# Schematic_TSC.net
KiCad netlist of a schematic drawn in EAGLE
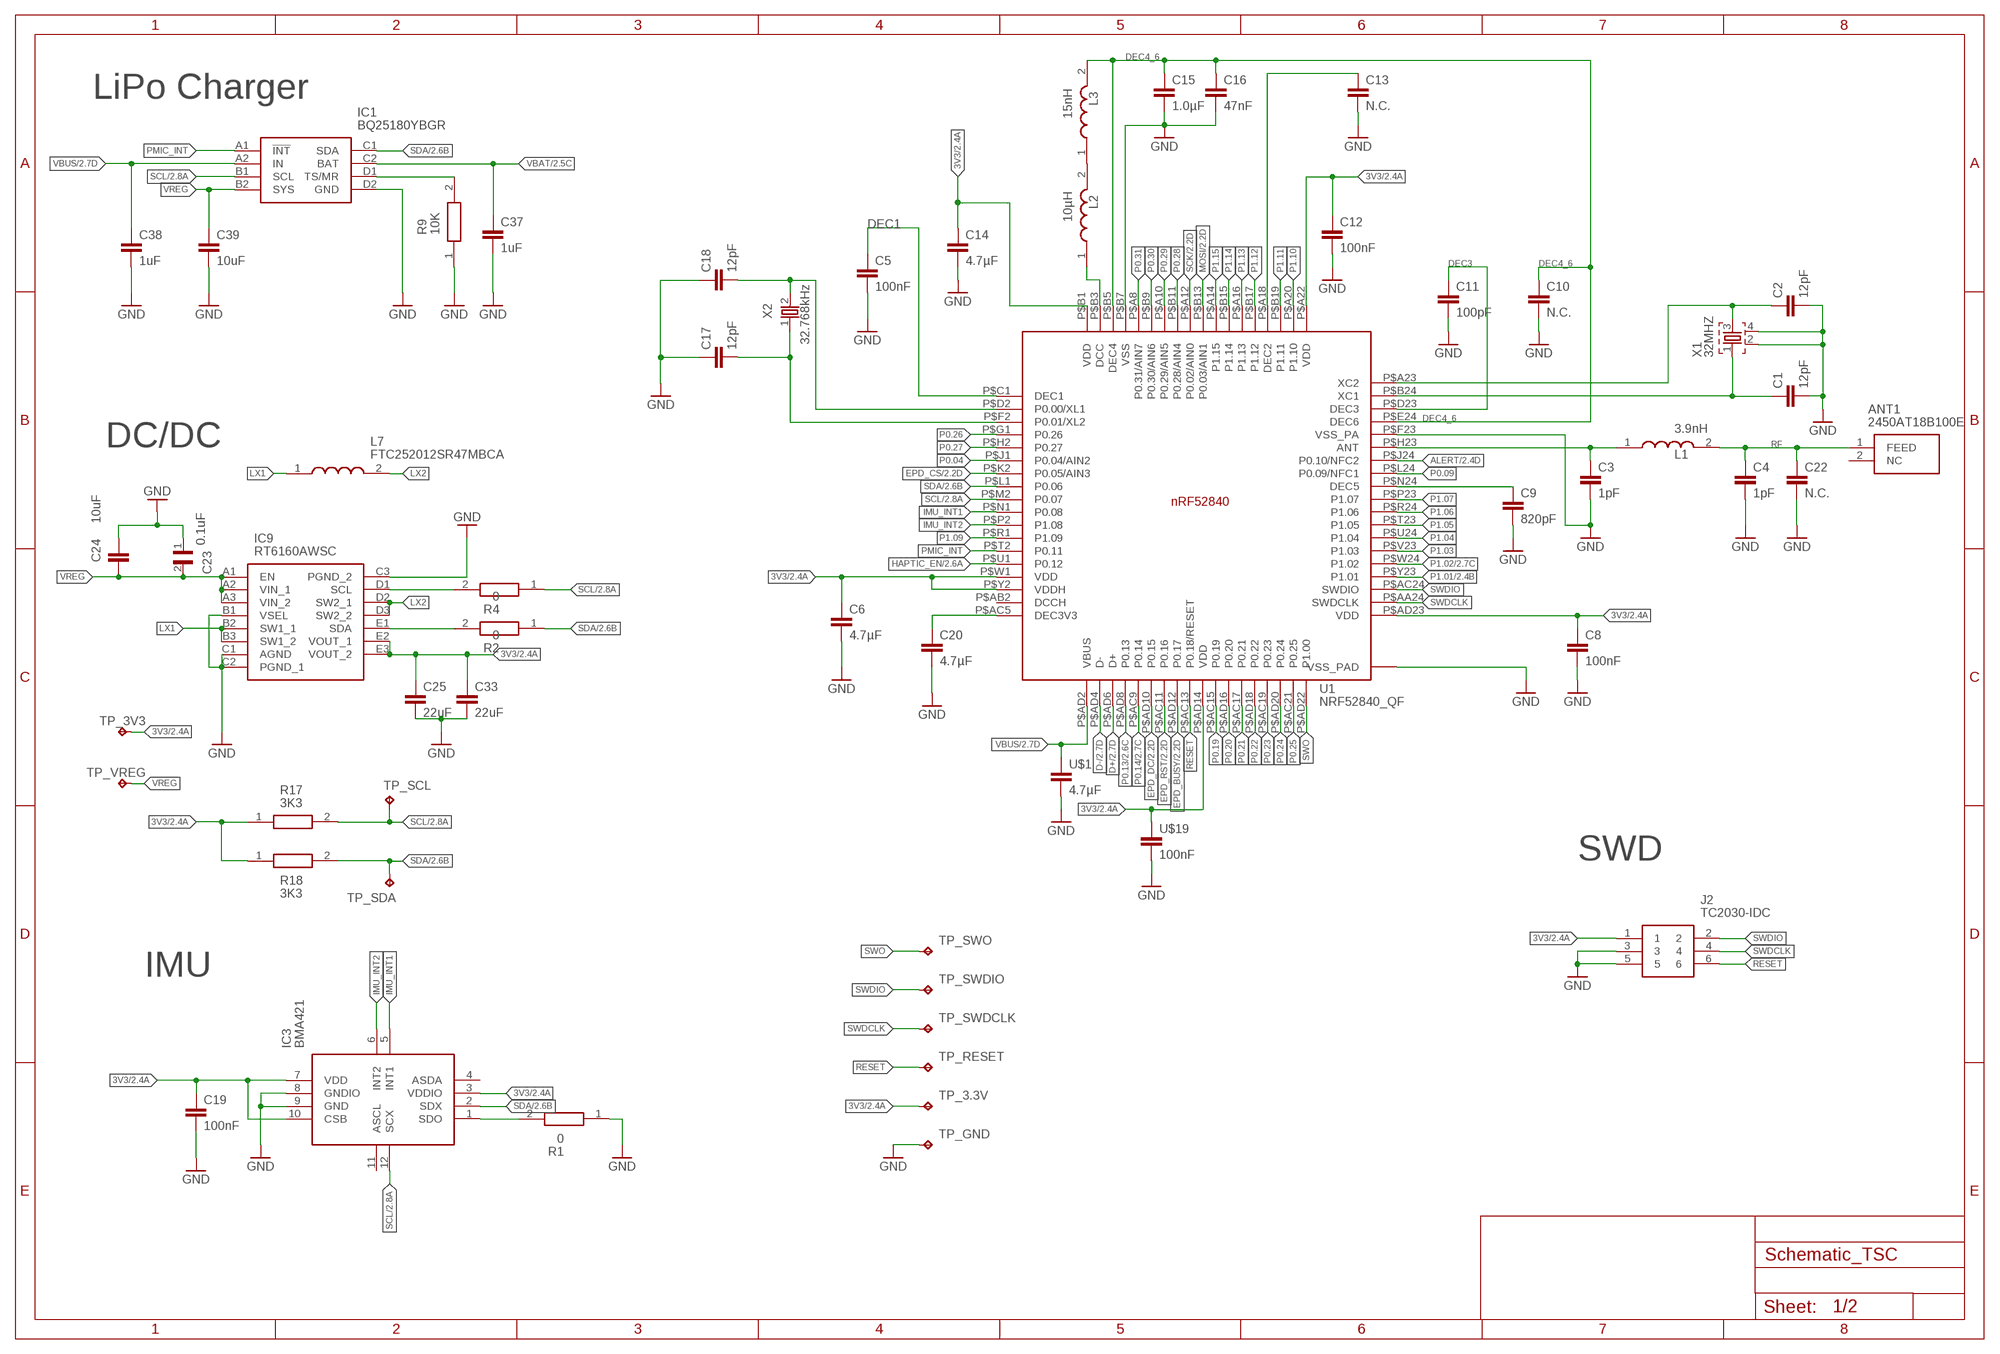
[diagram p0: schematic, sheet 1]
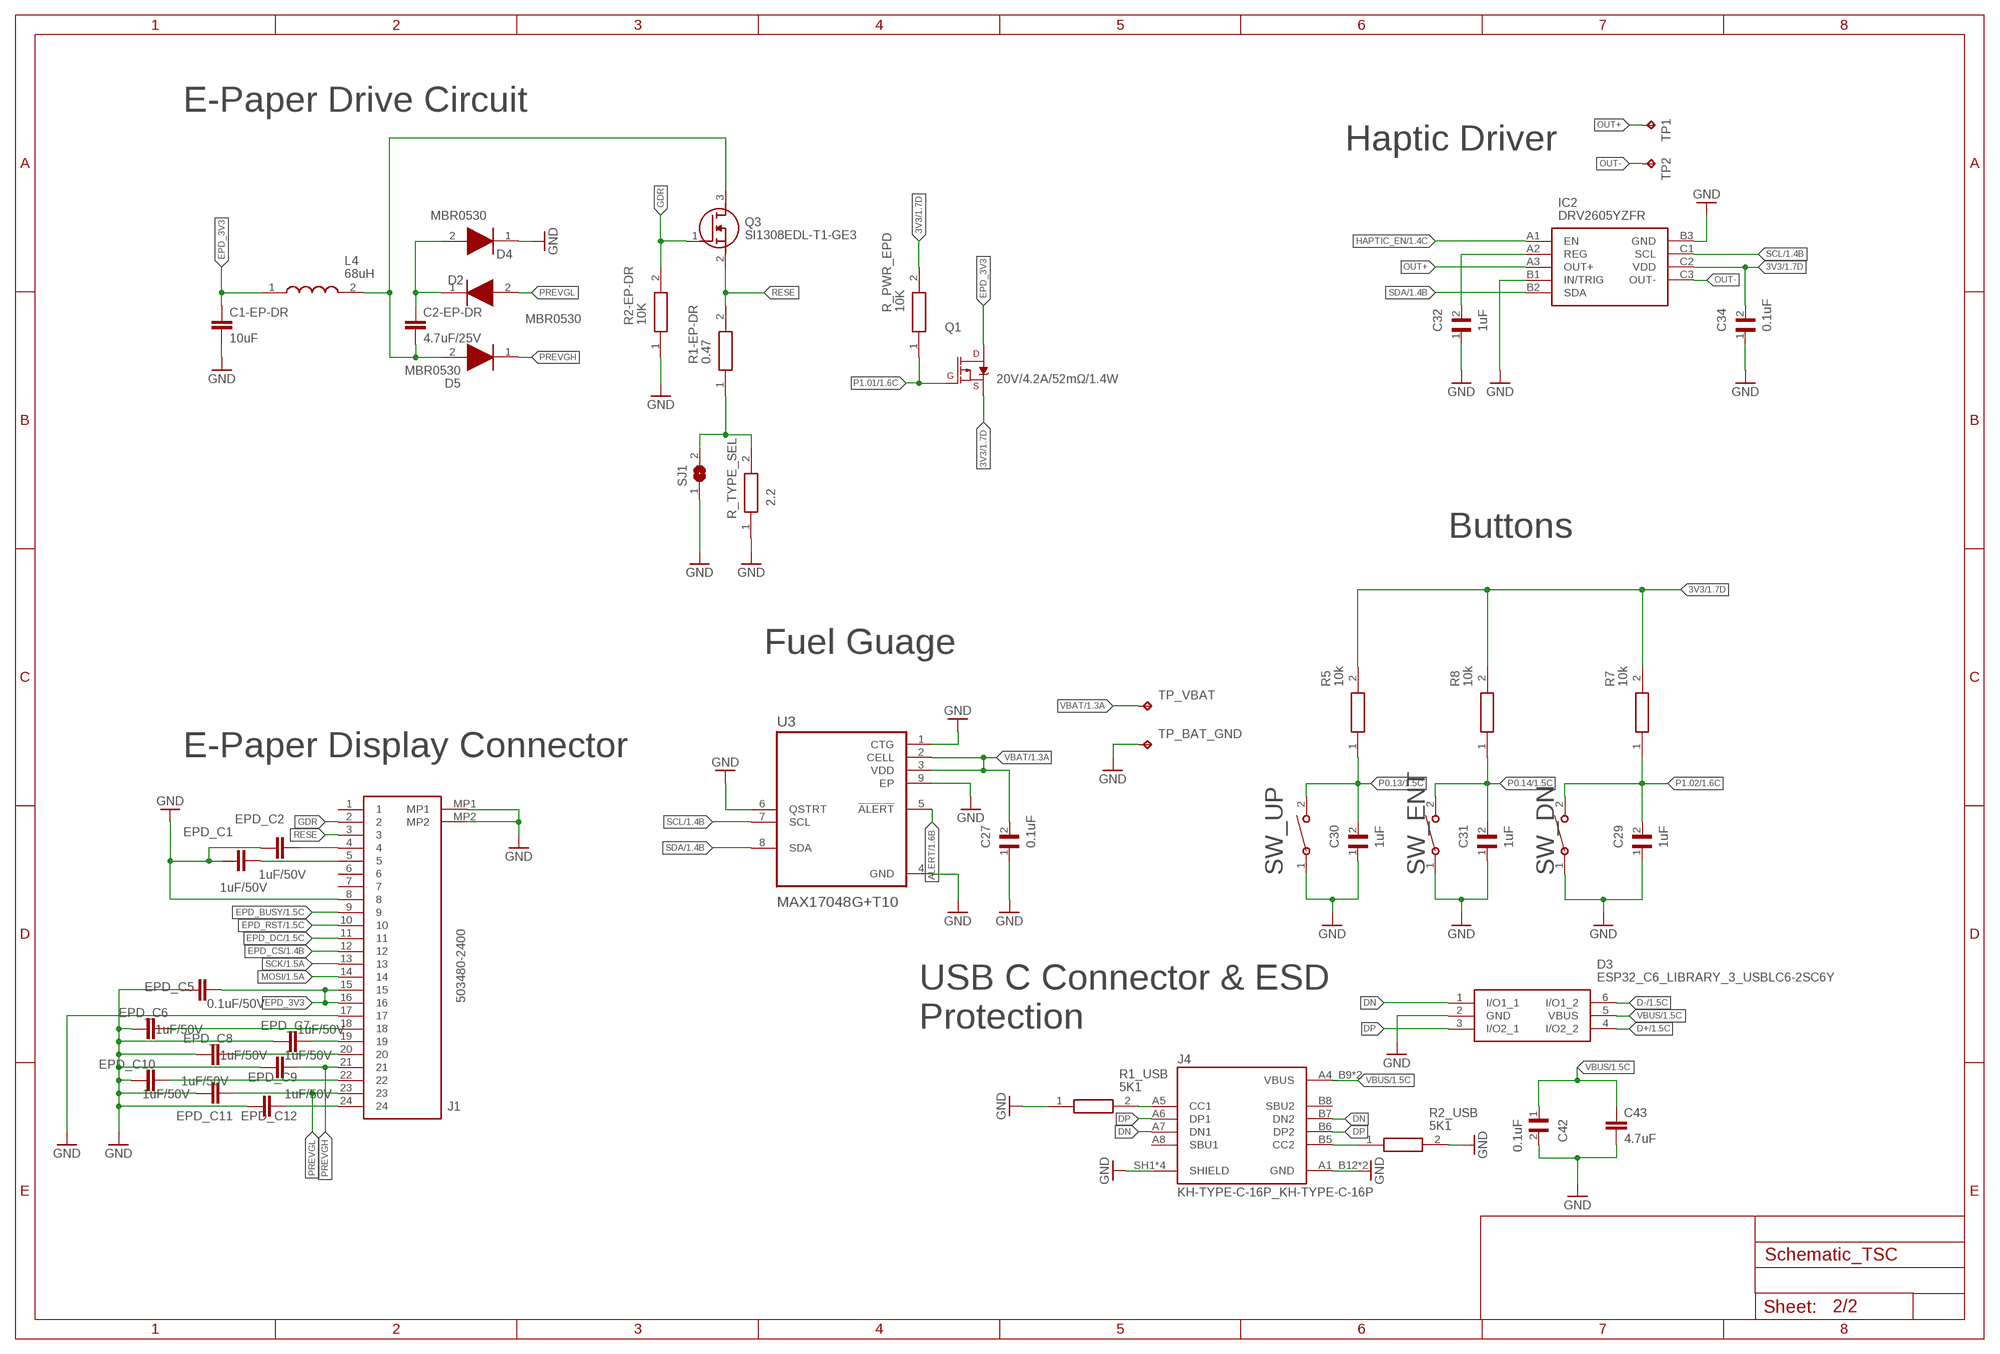
[diagram p1: schematic, sheet 2]

(export (version "E")
  (design (tool "Eeschema 10.0.6"))
  (components
    (comp (ref "ANT1")
      (value "2450AT18B100E")
      (footprint "eagle-import:2450AT18B100E_ANTC3216X140N")
      (fields (field (name "MOUSER_PART_NUMBER") "609-2450AT18B100E"))
      (libsource (lib "eagle-import") (part "2450AT18B100E_2450AT18B100E"))
    )
    (comp (ref "C1")
      (value "12pF")
      (footprint "eagle-import:NORDIC_NRF_3_RESC0201_L")
      (libsource (lib "eagle-import") (part "NORDIC_NRF_3_CAPACITOR_0201_L"))
    )
    (comp (ref "C2")
      (value "12pF")
      (footprint "eagle-import:NORDIC_NRF_3_RESC0201_L")
      (libsource (lib "eagle-import") (part "NORDIC_NRF_3_CAPACITOR_0201_L"))
    )
    (comp (ref "C3")
      (value "1pF")
      (footprint "eagle-import:NORDIC_NRF_3_RESC0201_L")
      (libsource (lib "eagle-import") (part "NORDIC_NRF_3_CAPACITOR_0201_L"))
    )
    (comp (ref "C4")
      (value "1pF")
      (footprint "eagle-import:NORDIC_NRF_3_RESC0201_L")
      (libsource (lib "eagle-import") (part "NORDIC_NRF_3_CAPACITOR_0201_L"))
    )
    (comp (ref "C5")
      (value "100nF")
      (footprint "eagle-import:NORDIC_NRF_3_RESC0201_L")
      (libsource (lib "eagle-import") (part "NORDIC_NRF_3_CAPACITOR_0201_L"))
    )
    (comp (ref "C6")
      (value "4.7µF")
      (footprint "eagle-import:NORDIC_NRF_3_RESC0201_L")
      (libsource (lib "eagle-import") (part "NORDIC_NRF_3_CAPACITOR_0201_L"))
    )
    (comp (ref "C8")
      (value "100nF")
      (footprint "eagle-import:NORDIC_NRF_3_RESC0201_L")
      (libsource (lib "eagle-import") (part "NORDIC_NRF_3_CAPACITOR_0201_L"))
    )
    (comp (ref "C9")
      (value "820pF")
      (footprint "eagle-import:NORDIC_NRF_3_RESC0201_L")
      (libsource (lib "eagle-import") (part "NORDIC_NRF_3_CAPACITOR_0201_L"))
    )
    (comp (ref "C10")
      (value "N.C.")
      (footprint "eagle-import:NORDIC_NRF_3_RESC0201_L")
      (libsource (lib "eagle-import") (part "NORDIC_NRF_3_CAPACITOR_0201_L"))
    )
    (comp (ref "C11")
      (value "100pF")
      (footprint "eagle-import:NORDIC_NRF_3_RESC0201_L")
      (libsource (lib "eagle-import") (part "NORDIC_NRF_3_CAPACITOR_0201_L"))
    )
    (comp (ref "C12")
      (value "100nF")
      (footprint "eagle-import:NORDIC_NRF_3_RESC0201_L")
      (libsource (lib "eagle-import") (part "NORDIC_NRF_3_CAPACITOR_0201_L"))
    )
    (comp (ref "C13")
      (value "N.C.")
      (footprint "eagle-import:NORDIC_NRF_3_RESC0201_L")
      (libsource (lib "eagle-import") (part "NORDIC_NRF_3_CAPACITOR_0201_L"))
    )
    (comp (ref "C14")
      (value "4.7µF")
      (footprint "eagle-import:NORDIC_NRF_3_RESC0201_L")
      (libsource (lib "eagle-import") (part "NORDIC_NRF_3_CAPACITOR_0201_L"))
    )
    (comp (ref "C15")
      (value "1.0µF")
      (footprint "eagle-import:NORDIC_NRF_3_RESC0201_L")
      (libsource (lib "eagle-import") (part "NORDIC_NRF_3_CAPACITOR_0201_L"))
    )
    (comp (ref "C16")
      (value "47nF")
      (footprint "eagle-import:NORDIC_NRF_3_RESC0201_L")
      (libsource (lib "eagle-import") (part "NORDIC_NRF_3_CAPACITOR_0201_L"))
    )
    (comp (ref "C17")
      (value "12pF")
      (footprint "eagle-import:NORDIC_NRF_3_RESC0201_L")
      (libsource (lib "eagle-import") (part "NORDIC_NRF_3_CAPACITOR_0201_L"))
    )
    (comp (ref "C18")
      (value "12pF")
      (footprint "eagle-import:NORDIC_NRF_3_RESC0201_L")
      (libsource (lib "eagle-import") (part "NORDIC_NRF_3_CAPACITOR_0201_L"))
    )
    (comp (ref "C19")
      (value "100nF")
      (footprint "eagle-import:NORDIC_NRF_3_RESC0201_L")
      (libsource (lib "eagle-import") (part "NORDIC_NRF_3_CAPACITOR_0201_L"))
    )
    (comp (ref "C20")
      (value "4.7µF")
      (footprint "eagle-import:NORDIC_NRF_3_RESC0201_L")
      (libsource (lib "eagle-import") (part "NORDIC_NRF_3_CAPACITOR_0201_L"))
    )
    (comp (ref "C22")
      (value "N.C.")
      (footprint "eagle-import:NORDIC_NRF_3_RESC0201_L")
      (libsource (lib "eagle-import") (part "NORDIC_NRF_3_CAPACITOR_0201_L"))
    )
    (comp (ref "C23")
      (value "0.1uF")
      (footprint "eagle-import:GRM011R60J152KE01L_2_CAPC0201X13N")
      (fields (field (name "MF") "Murata") (field (name "MP") "GRM011R60J152KE01L"))
      (libsource (lib "eagle-import") (part "GRM011R60J152KE01L_2_GRM011R60J152KE01L"))
    )
    (comp (ref "C24")
      (value "10uF")
      (footprint "eagle-import:NORDIC_NRF_3_RESC0201_L")
      (libsource (lib "eagle-import") (part "NORDIC_NRF_3_CAPACITOR_0201_L"))
    )
    (comp (ref "C25")
      (value "22uF")
      (footprint "eagle-import:NORDIC_NRF_3_RESC0201_L")
      (libsource (lib "eagle-import") (part "NORDIC_NRF_3_CAPACITOR_0201_L"))
    )
    (comp (ref "C33")
      (value "22uF")
      (footprint "eagle-import:NORDIC_NRF_3_RESC0201_L")
      (libsource (lib "eagle-import") (part "NORDIC_NRF_3_CAPACITOR_0201_L"))
    )
    (comp (ref "C37")
      (value "1uF")
      (footprint "eagle-import:NORDIC_NRF_3_RESC0201_L")
      (libsource (lib "eagle-import") (part "NORDIC_NRF_3_CAPACITOR_0201_L"))
    )
    (comp (ref "C38")
      (value "1uF")
      (footprint "eagle-import:NORDIC_NRF_3_RESC0201_L")
      (libsource (lib "eagle-import") (part "NORDIC_NRF_3_CAPACITOR_0201_L"))
    )
    (comp (ref "C39")
      (value "10uF")
      (footprint "eagle-import:NORDIC_NRF_3_RESC0201_L")
      (libsource (lib "eagle-import") (part "NORDIC_NRF_3_CAPACITOR_0201_L"))
    )
    (comp (ref "IC1")
      (value "BQ25180YBGR")
      (footprint "eagle-import:BQ25180YBGR_BGA8C40P2X4_100X155X50")
      (fields (field (name "MOUSER_PART_NUMBER") "595-BQ25180YBGR"))
      (libsource (lib "eagle-import") (part "BQ25180YBGR_BQ25180YBGR"))
    )
    (comp (ref "IC3")
      (value "BMA421")
      (footprint "eagle-import:BMA423_BMA423")
      (fields (field (name "ARROW_PART_NUMBER") "BMA423") (field (name "MOUSER_PART_NUMBER") "262-BMA423"))
      (libsource (lib "eagle-import") (part "BMA423_BMA423"))
    )
    (comp (ref "IC9")
      (value "RT6160AWSC")
      (footprint "eagle-import:RT6160AWSC_BGA15C40P3X5_140X230X60")
      (fields (field (name "MOUSER_PART_NUMBER") "835-RT6160AWSC"))
      (libsource (lib "eagle-import") (part "RT6160AWSC_RT6160AWSC"))
    )
    (comp (ref "J2")
      (value "TC2030-IDC")
      (footprint "eagle-import:TC2030-IDC_TC2030IDC")
      (libsource (lib "eagle-import") (part "TC2030-IDC_TC2030-IDC"))
    )
    (comp (ref "L1")
      (value "3.9nH")
      (footprint "eagle-import:MLP2016SR47MT0S1_INDC2016X100N")
      (fields (field (name "MANUFACTURER_PART_NUMBER") "FTC252012SR47MBCA"))
      (libsource (lib "eagle-import") (part "MLP2016SR47MT0S1_FTC252012SR47MBCA"))
    )
    (comp (ref "L2")
      (value "10µH")
      (footprint "eagle-import:MLP2016SR47MT0S1_INDC2016X100N")
      (fields (field (name "MANUFACTURER_PART_NUMBER") "FTC252012SR47MBCA"))
      (libsource (lib "eagle-import") (part "MLP2016SR47MT0S1_FTC252012SR47MBCA"))
    )
    (comp (ref "L3")
      (value "15nH")
      (footprint "eagle-import:MLP2016SR47MT0S1_INDC2016X100N")
      (fields (field (name "MANUFACTURER_PART_NUMBER") "FTC252012SR47MBCA"))
      (libsource (lib "eagle-import") (part "MLP2016SR47MT0S1_FTC252012SR47MBCA"))
    )
    (comp (ref "L7")
      (value "FTC252012SR47MBCA")
      (footprint "eagle-import:MLP2016SR47MT0S1_INDC2016X100N")
      (libsource (lib "eagle-import") (part "MLP2016SR47MT0S1_FTC252012SR47MBCA"))
    )
    (comp (ref "R1")
      (value "0")
      (footprint "eagle-import:CPF0201D7K68C1_0201")
      (libsource (lib "eagle-import") (part "CPF0201D7K68C1_CPF0201D7K68C1"))
    )
    (comp (ref "R2")
      (value "0")
      (footprint "eagle-import:CPF0201D7K68C1_0201")
      (libsource (lib "eagle-import") (part "CPF0201D7K68C1_CPF0201D7K68C1"))
    )
    (comp (ref "R4")
      (value "0")
      (footprint "eagle-import:CPF0201D7K68C1_0201")
      (libsource (lib "eagle-import") (part "CPF0201D7K68C1_CPF0201D7K68C1"))
    )
    (comp (ref "R9")
      (value "10K")
      (footprint "eagle-import:CPF0201D7K68C1_0201")
      (libsource (lib "eagle-import") (part "CPF0201D7K68C1_CPF0201D7K68C1"))
    )
    (comp (ref "R17")
      (value "3K3")
      (footprint "eagle-import:CPF0201D7K68C1_0201")
      (libsource (lib "eagle-import") (part "CPF0201D7K68C1_CPF0201D7K68C1"))
    )
    (comp (ref "R18")
      (value "3K3")
      (footprint "eagle-import:CPF0201D7K68C1_0201")
      (libsource (lib "eagle-import") (part "CPF0201D7K68C1_CPF0201D7K68C1"))
    )
    (comp (ref "TP_3.3V")
      (value "HECTOR_WATCH_1_TPTP20R")
      (footprint "eagle-import:HECTOR_WATCH_1_TP20R")
      (libsource (lib "eagle-import") (part "HECTOR_WATCH_1_TPTP20R"))
    )
    (comp (ref "TP_3V3")
      (value "HECTOR_WATCH_1_TPTP20R")
      (footprint "eagle-import:HECTOR_WATCH_1_TP20R")
      (libsource (lib "eagle-import") (part "HECTOR_WATCH_1_TPTP20R"))
    )
    (comp (ref "TP_GND")
      (value "HECTOR_WATCH_1_TPTP20R")
      (footprint "eagle-import:HECTOR_WATCH_1_TP20R")
      (libsource (lib "eagle-import") (part "HECTOR_WATCH_1_TPTP20R"))
    )
    (comp (ref "TP_RESET")
      (value "HECTOR_WATCH_1_TPTP20R")
      (footprint "eagle-import:HECTOR_WATCH_1_TP20R")
      (libsource (lib "eagle-import") (part "HECTOR_WATCH_1_TPTP20R"))
    )
    (comp (ref "TP_SCL")
      (value "HECTOR_WATCH_1_TPTP20R")
      (footprint "eagle-import:HECTOR_WATCH_1_TP20R")
      (libsource (lib "eagle-import") (part "HECTOR_WATCH_1_TPTP20R"))
    )
    (comp (ref "TP_SDA")
      (value "HECTOR_WATCH_1_TPTP20R")
      (footprint "eagle-import:HECTOR_WATCH_1_TP20R")
      (libsource (lib "eagle-import") (part "HECTOR_WATCH_1_TPTP20R"))
    )
    (comp (ref "TP_SWDCLK")
      (value "HECTOR_WATCH_1_TPTP20R")
      (footprint "eagle-import:HECTOR_WATCH_1_TP20R")
      (libsource (lib "eagle-import") (part "HECTOR_WATCH_1_TPTP20R"))
    )
    (comp (ref "TP_SWDIO")
      (value "HECTOR_WATCH_1_TPTP20R")
      (footprint "eagle-import:HECTOR_WATCH_1_TP20R")
      (libsource (lib "eagle-import") (part "HECTOR_WATCH_1_TPTP20R"))
    )
    (comp (ref "TP_SWO")
      (value "HECTOR_WATCH_1_TPTP20R")
      (footprint "eagle-import:HECTOR_WATCH_1_TP20R")
      (libsource (lib "eagle-import") (part "HECTOR_WATCH_1_TPTP20R"))
    )
    (comp (ref "TP_VREG")
      (value "HECTOR_WATCH_1_TPTP20R")
      (footprint "eagle-import:HECTOR_WATCH_1_TP20R")
      (libsource (lib "eagle-import") (part "HECTOR_WATCH_1_TPTP20R"))
    )
    (comp (ref "U$1")
      (value "4.7µF")
      (footprint "eagle-import:NORDIC_NRF_3_RESC0201_L")
      (libsource (lib "eagle-import") (part "NORDIC_NRF_3_CAPACITOR_0201_L"))
    )
    (comp (ref "U$19")
      (value "100nF")
      (footprint "eagle-import:NORDIC_NRF_3_RESC0201_L")
      (libsource (lib "eagle-import") (part "NORDIC_NRF_3_CAPACITOR_0201_L"))
    )
    (comp (ref "U1")
      (value "NRF52840_QF")
      (footprint "eagle-import:NORDIC_NRF_4_AQFN50P700X700X85_HS-74N")
      (libsource (lib "eagle-import") (part "NORDIC_NRF_4_NRF52840_QF"))
    )
    (comp (ref "X1")
      (value "32MHZ")
      (footprint "eagle-import:NORDIC_NRF_BT-XTAL_2016_N")
      (libsource (lib "eagle-import") (part "NORDIC_NRF_XTAL_32MHZ"))
    )
    (comp (ref "X2")
      (value "32.768kHz")
      (footprint "eagle-import:NORDIC_NRF_1_XTAL_3215_N")
      (libsource (lib "eagle-import") (part "NORDIC_NRF_1_XTAL_32KHZ"))
    )
    (comp (ref "C1-EP-DR")
      (value "10uF")
      (footprint "eagle-import:NORDIC_NRF_3_RESC0201_L")
      (libsource (lib "eagle-import") (part "NORDIC_NRF_3_CAPACITOR_0201_L"))
    )
    (comp (ref "C2-EP-DR")
      (value "4.7uF/25V")
      (footprint "eagle-import:NORDIC_NRF_3_RESC0201_L")
      (libsource (lib "eagle-import") (part "NORDIC_NRF_3_CAPACITOR_0201_L"))
    )
    (comp (ref "C27")
      (value "0.1uF")
      (footprint "eagle-import:GRM011R60J152KE01L_2_CAPC0201X13N")
      (fields (field (name "MF") "Murata") (field (name "MP") "GRM011R60J152KE01L"))
      (libsource (lib "eagle-import") (part "GRM011R60J152KE01L_2_GRM011R60J152KE01L"))
    )
    (comp (ref "C29")
      (value "1uF")
      (footprint "eagle-import:GRM011R60J152KE01L_2_CAPC0201X13N")
      (fields (field (name "MF") "Murata") (field (name "MP") "GRM011R60J152KE01L"))
      (libsource (lib "eagle-import") (part "GRM011R60J152KE01L_2_GRM011R60J152KE01L"))
    )
    (comp (ref "C30")
      (value "1uF")
      (footprint "eagle-import:GRM011R60J152KE01L_2_CAPC0201X13N")
      (fields (field (name "MF") "Murata") (field (name "MP") "GRM011R60J152KE01L"))
      (libsource (lib "eagle-import") (part "GRM011R60J152KE01L_2_GRM011R60J152KE01L"))
    )
    (comp (ref "C31")
      (value "1uF")
      (footprint "eagle-import:GRM011R60J152KE01L_2_CAPC0201X13N")
      (fields (field (name "MF") "Murata") (field (name "MP") "GRM011R60J152KE01L"))
      (libsource (lib "eagle-import") (part "GRM011R60J152KE01L_2_GRM011R60J152KE01L"))
    )
    (comp (ref "C32")
      (value "1uF")
      (footprint "eagle-import:GRM011R60J152KE01L_2_CAPC0201X13N")
      (fields (field (name "MF") "Murata") (field (name "MP") "GRM011R60J152KE01L"))
      (libsource (lib "eagle-import") (part "GRM011R60J152KE01L_2_GRM011R60J152KE01L"))
    )
    (comp (ref "C34")
      (value "0.1uF")
      (footprint "eagle-import:GRM011R60J152KE01L_2_CAPC0201X13N")
      (fields (field (name "MF") "Murata") (field (name "MP") "GRM011R60J152KE01L"))
      (libsource (lib "eagle-import") (part "GRM011R60J152KE01L_2_GRM011R60J152KE01L"))
    )
    (comp (ref "C42")
      (value "0.1uF")
      (footprint "eagle-import:GRM011R60J152KE01L_2_CAPC0201X13N")
      (fields (field (name "MF") "Murata") (field (name "MP") "GRM011R60J152KE01L"))
      (libsource (lib "eagle-import") (part "GRM011R60J152KE01L_2_GRM011R60J152KE01L"))
    )
    (comp (ref "C43")
      (value "4.7uF")
      (footprint "eagle-import:NORDIC_NRF_3_RESC0201_L")
      (libsource (lib "eagle-import") (part "NORDIC_NRF_3_CAPACITOR_0201_L"))
    )
    (comp (ref "D2")
      (value "MBR0530")
      (footprint "eagle-import:ESP32_C6_LIBRARY_5_SOD3716X135N")
      (fields (field (name "MF") "ON Semiconductor"))
      (libsource (lib "eagle-import") (part "ESP32_C6_LIBRARY_5_MBR0530"))
    )
    (comp (ref "D3")
      (value "ESP32_C6_LIBRARY_3_USBLC6-2SC6Y")
      (footprint "eagle-import:ESP32_C6_LIBRARY_3_SOT95P280X145-6N")
      (fields (field (name "MF") "STMicroelectronics") (field (name "MP") "USBLC6-2SC6Y"))
      (libsource (lib "eagle-import") (part "ESP32_C6_LIBRARY_3_USBLC6-2SC6Y"))
    )
    (comp (ref "D4")
      (value "MBR0530")
      (footprint "eagle-import:ESP32_C6_LIBRARY_5_SOD3716X135N")
      (fields (field (name "MF") "ON Semiconductor"))
      (libsource (lib "eagle-import") (part "ESP32_C6_LIBRARY_5_MBR0530"))
    )
    (comp (ref "D5")
      (value "MBR0530")
      (footprint "eagle-import:ESP32_C6_LIBRARY_5_SOD3716X135N")
      (fields (field (name "MF") "ON Semiconductor"))
      (libsource (lib "eagle-import") (part "ESP32_C6_LIBRARY_5_MBR0530"))
    )
    (comp (ref "EPD_C1")
      (value "1uF/50V")
      (footprint "eagle-import:NORDIC_NRF_3_RESC0201_L")
      (libsource (lib "eagle-import") (part "NORDIC_NRF_3_CAPACITOR_0201_L"))
    )
    (comp (ref "EPD_C2")
      (value "1uF/50V")
      (footprint "eagle-import:NORDIC_NRF_3_RESC0201_L")
      (libsource (lib "eagle-import") (part "NORDIC_NRF_3_CAPACITOR_0201_L"))
    )
    (comp (ref "EPD_C5")
      (value "0.1uF/50V")
      (footprint "eagle-import:NORDIC_NRF_3_RESC0201_L")
      (libsource (lib "eagle-import") (part "NORDIC_NRF_3_CAPACITOR_0201_L"))
    )
    (comp (ref "EPD_C6")
      (value "1uF/50V")
      (footprint "eagle-import:NORDIC_NRF_3_RESC0201_L")
      (libsource (lib "eagle-import") (part "NORDIC_NRF_3_CAPACITOR_0201_L"))
    )
    (comp (ref "EPD_C7")
      (value "1uF/50V")
      (footprint "eagle-import:NORDIC_NRF_3_RESC0201_L")
      (libsource (lib "eagle-import") (part "NORDIC_NRF_3_CAPACITOR_0201_L"))
    )
    (comp (ref "EPD_C8")
      (value "1uF/50V")
      (footprint "eagle-import:NORDIC_NRF_3_RESC0201_L")
      (libsource (lib "eagle-import") (part "NORDIC_NRF_3_CAPACITOR_0201_L"))
    )
    (comp (ref "EPD_C9")
      (value "1uF/50V")
      (footprint "eagle-import:NORDIC_NRF_3_RESC0201_L")
      (libsource (lib "eagle-import") (part "NORDIC_NRF_3_CAPACITOR_0201_L"))
    )
    (comp (ref "EPD_C10")
      (value "1uF/50V")
      (footprint "eagle-import:NORDIC_NRF_3_RESC0201_L")
      (libsource (lib "eagle-import") (part "NORDIC_NRF_3_CAPACITOR_0201_L"))
    )
    (comp (ref "EPD_C11")
      (value "1uF/50V")
      (footprint "eagle-import:NORDIC_NRF_3_RESC0201_L")
      (libsource (lib "eagle-import") (part "NORDIC_NRF_3_CAPACITOR_0201_L"))
    )
    (comp (ref "EPD_C12")
      (value "1uF/50V")
      (footprint "eagle-import:NORDIC_NRF_3_RESC0201_L")
      (libsource (lib "eagle-import") (part "NORDIC_NRF_3_CAPACITOR_0201_L"))
    )
    (comp (ref "IC2")
      (value "DRV2605YZFR")
      (footprint "eagle-import:DRV2605YZFR_BGA9C50P3X3_144X144X62")
      (libsource (lib "eagle-import") (part "DRV2605YZFR_DRV2605YZFR"))
    )
    (comp (ref "J1")
      (value "503480-2400")
      (footprint "eagle-import:503480-2400_5034802400")
      (fields (field (name "MOUSER_PART_NUMBER") "538-503480-2400"))
      (libsource (lib "eagle-import") (part "503480-2400_503480-2400"))
    )
    (comp (ref "J4")
      (value "KH-TYPE-C-16P_KH-TYPE-C-16P")
      (footprint "eagle-import:KH-TYPE-C-16P_KINGHELM_KH-TYPE-C-16P")
      (fields (field (name "MF") "kinghelm") (field (name "MP") "KH-TYPE-C-16P"))
      (libsource (lib "eagle-import") (part "KH-TYPE-C-16P_KH-TYPE-C-16P"))
    )
    (comp (ref "L4")
      (value "68uH")
      (footprint "eagle-import:MLP2016SR47MT0S1_INDC2016X100N")
      (fields (field (name "MANUFACTURER_PART_NUMBER") "FTC252012SR47MBCA"))
      (libsource (lib "eagle-import") (part "MLP2016SR47MT0S1_FTC252012SR47MBCA"))
    )
    (comp (ref "Q1")
      (value "20V/4.2A/52mΩ/1.4W")
      (footprint "eagle-import:ESP32_C6_LIBRARY_4_ESP32_C6_LIBRARY_4_ESP32_C6_LIBRARY_4_ESP32_C6_LIBRARY_4_ESP32_WROVER_SPARKFUN-DISCRETESEMI_SOT23-3")
      (libsource (lib "eagle-import") (part "ESP32_C6_LIBRARY_4_ESP32_WROVER_SPARKFUN-DISCRETESEMI_MOSFET_PCH-DMG2305UX-7"))
    )
    (comp (ref "Q3")
      (value "SI1308EDL-T1-GE3")
      (footprint "eagle-import:ESP32_C6_LIBRARY_6_SOT65P210X110-3N")
      (fields (field (name "MF") "Vishay Siliconix"))
      (libsource (lib "eagle-import") (part "ESP32_C6_LIBRARY_6_SI1308EDL-T1-GE3"))
    )
    (comp (ref "R1-EP-DR")
      (value "0.47")
      (footprint "eagle-import:CPF0201D7K68C1_0201")
      (libsource (lib "eagle-import") (part "CPF0201D7K68C1_CPF0201D7K68C1"))
    )
    (comp (ref "R1_USB")
      (value "5K1")
      (footprint "eagle-import:CPF0201D7K68C1_0201")
      (libsource (lib "eagle-import") (part "CPF0201D7K68C1_CPF0201D7K68C1"))
    )
    (comp (ref "R2-EP-DR")
      (value "10K")
      (footprint "eagle-import:CPF0201D7K68C1_0201")
      (libsource (lib "eagle-import") (part "CPF0201D7K68C1_CPF0201D7K68C1"))
    )
    (comp (ref "R2_USB")
      (value "5K1")
      (footprint "eagle-import:CPF0201D7K68C1_0201")
      (libsource (lib "eagle-import") (part "CPF0201D7K68C1_CPF0201D7K68C1"))
    )
    (comp (ref "R5")
      (value "10k")
      (footprint "eagle-import:CPF0201D7K68C1_0201")
      (libsource (lib "eagle-import") (part "CPF0201D7K68C1_CPF0201D7K68C1"))
    )
    (comp (ref "R7")
      (value "10k")
      (footprint "eagle-import:CPF0201D7K68C1_0201")
      (libsource (lib "eagle-import") (part "CPF0201D7K68C1_CPF0201D7K68C1"))
    )
    (comp (ref "R8")
      (value "10k")
      (footprint "eagle-import:CPF0201D7K68C1_0201")
      (libsource (lib "eagle-import") (part "CPF0201D7K68C1_CPF0201D7K68C1"))
    )
    (comp (ref "R_PWR_EPD")
      (value "10K")
      (footprint "eagle-import:CPF0201D7K68C1_0201")
      (libsource (lib "eagle-import") (part "CPF0201D7K68C1_CPF0201D7K68C1"))
    )
    (comp (ref "R_TYPE_SEL")
      (value "2.2")
      (footprint "eagle-import:CPF0201D7K68C1_0201")
      (libsource (lib "eagle-import") (part "CPF0201D7K68C1_CPF0201D7K68C1"))
    )
    (comp (ref "SJ1")
      (value "ESP32_C6_LIBRARY_7_JUMPER_SJ")
      (footprint "eagle-import:ESP32_C6_LIBRARY_7_JUMPER_SJ")
      (libsource (lib "eagle-import") (part "ESP32_C6_LIBRARY_7_JUMPER_SJ"))
    )
    (comp (ref "SW_DN")
      (value "2025-10-22_07-23-44_LIBRARY_EVP-AKE31ASW_EVP-AKE31A_PAN")
      (footprint "eagle-import:2025-10-22_07-23-44_LIBRARY_SW_EVP-AKE31A_PAN")
      (fields
        (field (name "MANUFACTURER_PART_NUMBER") "EVP-AKE31A")
        (field (name "COPYRIGHT") "Copyright (C) 2025 Ultra Librarian. All rights reserved.")
      )
      (libsource (lib "eagle-import") (part "2025-10-22_07-23-44_LIBRARY_EVP-AKE31ASW_EVP-AKE31A_PAN"))
    )
    (comp (ref "SW_ENT")
      (value "2025-10-22_07-23-44_LIBRARY_EVP-AKE31ASW_EVP-AKE31A_PAN")
      (footprint "eagle-import:2025-10-22_07-23-44_LIBRARY_SW_EVP-AKE31A_PAN")
      (fields
        (field (name "MANUFACTURER_PART_NUMBER") "EVP-AKE31A")
        (field (name "COPYRIGHT") "Copyright (C) 2025 Ultra Librarian. All rights reserved.")
      )
      (libsource (lib "eagle-import") (part "2025-10-22_07-23-44_LIBRARY_EVP-AKE31ASW_EVP-AKE31A_PAN"))
    )
    (comp (ref "SW_UP")
      (value "2025-10-22_07-23-44_LIBRARY_EVP-AKE31ASW_EVP-AKE31A_PAN")
      (footprint "eagle-import:2025-10-22_07-23-44_LIBRARY_SW_EVP-AKE31A_PAN")
      (fields
        (field (name "MANUFACTURER_PART_NUMBER") "EVP-AKE31A")
        (field (name "COPYRIGHT") "Copyright (C) 2025 Ultra Librarian. All rights reserved.")
      )
      (libsource (lib "eagle-import") (part "2025-10-22_07-23-44_LIBRARY_EVP-AKE31ASW_EVP-AKE31A_PAN"))
    )
    (comp (ref "TP1")
      (value "HECTOR_WATCH_1_TPTP20R")
      (footprint "eagle-import:HECTOR_WATCH_1_TP20R")
      (libsource (lib "eagle-import") (part "HECTOR_WATCH_1_TPTP20R"))
    )
    (comp (ref "TP2")
      (value "HECTOR_WATCH_1_TPTP20R")
      (footprint "eagle-import:HECTOR_WATCH_1_TP20R")
      (libsource (lib "eagle-import") (part "HECTOR_WATCH_1_TPTP20R"))
    )
    (comp (ref "TP_BAT_GND")
      (value "HECTOR_WATCH_1_TPTP20R")
      (footprint "eagle-import:HECTOR_WATCH_1_TP20R")
      (libsource (lib "eagle-import") (part "HECTOR_WATCH_1_TPTP20R"))
    )
    (comp (ref "TP_VBAT")
      (value "HECTOR_WATCH_1_TPTP20R")
      (footprint "eagle-import:HECTOR_WATCH_1_TP20R")
      (libsource (lib "eagle-import") (part "HECTOR_WATCH_1_TPTP20R"))
    )
    (comp (ref "U3")
      (value "MAX17048G+T10")
      (footprint "eagle-import:ESP32_C6_LIBRARY_SON50P200X200X80-9N")
      (fields (field (name "MF") "Analog Devices"))
      (libsource (lib "eagle-import") (part "ESP32_C6_LIBRARY_MAX17048G+T10"))
    )
  )
  (nets
    (net (code "1") (name "3V3{slash}1.7D") (class "Default")
      (node (ref "C34") (pin "2") (pinfunction "2_2") (pintype "passive"))
      (node (ref "IC2") (pin "C2") (pinfunction "VDD_C2") (pintype "bidirectional"))
      (node (ref "Q1") (pin "2") (pinfunction "S_2") (pintype "bidirectional"))
      (node (ref "R5") (pin "2") (pinfunction "2_2") (pintype "bidirectional"))
      (node (ref "R7") (pin "2") (pinfunction "2_2") (pintype "bidirectional"))
      (node (ref "R8") (pin "2") (pinfunction "2_2") (pintype "bidirectional"))
      (node (ref "R_PWR_EPD") (pin "2") (pinfunction "2_2") (pintype "bidirectional"))
    )
    (net (code "2") (name "3V3{slash}2.4A") (class "Default")
      (node (ref "C12") (pin "1") (pinfunction "1_1") (pintype "passive"))
      (node (ref "C14") (pin "1") (pinfunction "1_1") (pintype "passive"))
      (node (ref "C19") (pin "1") (pinfunction "1_1") (pintype "passive"))
      (node (ref "C25") (pin "1") (pinfunction "1_1") (pintype "passive"))
      (node (ref "C33") (pin "1") (pinfunction "1_1") (pintype "passive"))
      (node (ref "C6") (pin "1") (pinfunction "1_1") (pintype "passive"))
      (node (ref "C8") (pin "1") (pinfunction "1_1") (pintype "passive"))
      (node (ref "IC3") (pin "10") (pinfunction "CSB_10") (pintype "bidirectional"))
      (node (ref "IC3") (pin "3") (pinfunction "VDDIO_3") (pintype "bidirectional"))
      (node (ref "IC3") (pin "7") (pinfunction "VDD_7") (pintype "bidirectional"))
      (node (ref "IC9") (pin "E2") (pinfunction "VOUT_1_E2") (pintype "bidirectional"))
      (node (ref "IC9") (pin "E3") (pinfunction "VOUT_2_E3") (pintype "bidirectional"))
      (node (ref "J2") (pin "1") (pinfunction "1_1") (pintype "bidirectional"))
      (node (ref "R17") (pin "1") (pinfunction "1_1") (pintype "bidirectional"))
      (node (ref "R18") (pin "1") (pinfunction "1_1") (pintype "bidirectional"))
      (node (ref "TP_3.3V") (pin "TP") (pinfunction "TP_TP") (pintype "input"))
      (node (ref "TP_3V3") (pin "TP") (pinfunction "TP_TP") (pintype "input"))
      (node (ref "U$19") (pin "1") (pinfunction "1_1") (pintype "passive"))
      (node (ref "U1") (pin "P$A22") (pinfunction "VDD_P$A22") (pintype "power_in"))
      (node (ref "U1") (pin "P$AD14") (pinfunction "VDD_P$AD14") (pintype "power_in"))
      (node (ref "U1") (pin "P$AD23") (pinfunction "VDD_P$AD23") (pintype "power_in"))
      (node (ref "U1") (pin "P$B1") (pinfunction "VDD_P$B1") (pintype "power_in"))
      (node (ref "U1") (pin "P$W1") (pinfunction "VDD_P$W1") (pintype "power_in"))
      (node (ref "U1") (pin "P$Y2") (pinfunction "VDDH_P$Y2") (pintype "power_in"))
    )
    (net (code "3") (name "ALERT") (class "Default")
      (node (ref "U1") (pin "P$J24") (pinfunction "P0.10/NFC2_P$J24") (pintype "bidirectional"))
      (node (ref "U3") (pin "5") (pinfunction "~{ALERT}_5") (pintype "output"))
    )
    (net (code "4") (name "D+") (class "Default")
      (node (ref "D3") (pin "4") (pinfunction "I/O2_2_4") (pintype "bidirectional"))
      (node (ref "U1") (pin "P$AD6") (pinfunction "D+_P$AD6") (pintype "bidirectional"))
    )
    (net (code "5") (name "D-") (class "Default")
      (node (ref "D3") (pin "6") (pinfunction "I/O1_2_6") (pintype "bidirectional"))
      (node (ref "U1") (pin "P$AD4") (pinfunction "D-_P$AD4") (pintype "bidirectional"))
    )
    (net (code "6") (name "DEC1") (class "Default")
      (node (ref "C5") (pin "1") (pinfunction "1_1") (pintype "passive"))
      (node (ref "U1") (pin "P$C1") (pinfunction "DEC1_P$C1") (pintype "power_in"))
    )
    (net (code "7") (name "DEC3") (class "Default")
      (node (ref "C11") (pin "1") (pinfunction "1_1") (pintype "passive"))
      (node (ref "U1") (pin "P$D23") (pinfunction "DEC3_P$D23") (pintype "bidirectional"))
    )
    (net (code "8") (name "DEC4_6") (class "Default")
      (node (ref "C10") (pin "1") (pinfunction "1_1") (pintype "passive"))
      (node (ref "C15") (pin "1") (pinfunction "1_1") (pintype "passive"))
      (node (ref "C16") (pin "1") (pinfunction "1_1") (pintype "passive"))
      (node (ref "L3") (pin "2") (pinfunction "2_2") (pintype "bidirectional"))
      (node (ref "U1") (pin "P$B5") (pinfunction "DEC4_P$B5") (pintype "power_in"))
      (node (ref "U1") (pin "P$E24") (pinfunction "DEC6_P$E24") (pintype "bidirectional"))
    )
    (net (code "9") (name "DN") (class "Default")
      (node (ref "D3") (pin "1") (pinfunction "I/O1_1_1") (pintype "bidirectional"))
      (node (ref "J4") (pin "A7") (pinfunction "DN1_A7") (pintype "bidirectional"))
      (node (ref "J4") (pin "B7") (pinfunction "DN2_B7") (pintype "bidirectional"))
    )
    (net (code "10") (name "DP") (class "Default")
      (node (ref "D3") (pin "3") (pinfunction "I/O2_1_3") (pintype "bidirectional"))
      (node (ref "J4") (pin "A6") (pinfunction "DP1_A6") (pintype "bidirectional"))
      (node (ref "J4") (pin "B6") (pinfunction "DP2_B6") (pintype "bidirectional"))
    )
    (net (code "11") (name "EPD_3V3") (class "Default")
      (node (ref "C1-EP-DR") (pin "1") (pinfunction "1_1") (pintype "passive"))
      (node (ref "EPD_C5") (pin "2") (pinfunction "2_2") (pintype "passive"))
      (node (ref "J1") (pin "15") (pinfunction "15_15") (pintype "bidirectional"))
      (node (ref "J1") (pin "16") (pinfunction "16_16") (pintype "bidirectional"))
      (node (ref "L4") (pin "1") (pinfunction "1_1") (pintype "bidirectional"))
      (node (ref "Q1") (pin "3") (pinfunction "D_3") (pintype "bidirectional"))
    )
    (net (code "12") (name "EPD_BUSY") (class "Default")
      (node (ref "J1") (pin "9") (pinfunction "9_9") (pintype "bidirectional"))
      (node (ref "U1") (pin "P$AD12") (pinfunction "P0.17_P$AD12") (pintype "bidirectional"))
    )
    (net (code "13") (name "EPD_CS") (class "Default")
      (node (ref "J1") (pin "12") (pinfunction "12_12") (pintype "bidirectional"))
      (node (ref "U1") (pin "P$K2") (pinfunction "P0.05/AIN3_P$K2") (pintype "bidirectional"))
    )
    (net (code "14") (name "EPD_DC") (class "Default")
      (node (ref "J1") (pin "11") (pinfunction "11_11") (pintype "bidirectional"))
      (node (ref "U1") (pin "P$AD10") (pinfunction "P0.15_P$AD10") (pintype "bidirectional"))
    )
    (net (code "15") (name "EPD_RST") (class "Default")
      (node (ref "J1") (pin "10") (pinfunction "10_10") (pintype "bidirectional"))
      (node (ref "U1") (pin "P$AC11") (pinfunction "P0.16_P$AC11") (pintype "bidirectional"))
    )
    (net (code "16") (name "GDR") (class "Default")
      (node (ref "J1") (pin "2") (pinfunction "2_2") (pintype "bidirectional"))
      (node (ref "Q3") (pin "1") (pinfunction "G_1") (pintype "bidirectional"))
      (node (ref "R2-EP-DR") (pin "2") (pinfunction "2_2") (pintype "bidirectional"))
    )
    (net (code "17") (name "GND") (class "Default")
      (node (ref "C1") (pin "2") (pinfunction "2_2") (pintype "passive"))
      (node (ref "C1-EP-DR") (pin "2") (pinfunction "2_2") (pintype "passive"))
      (node (ref "C10") (pin "2") (pinfunction "2_2") (pintype "passive"))
      (node (ref "C11") (pin "2") (pinfunction "2_2") (pintype "passive"))
      (node (ref "C12") (pin "2") (pinfunction "2_2") (pintype "passive"))
      (node (ref "C13") (pin "2") (pinfunction "2_2") (pintype "passive"))
      (node (ref "C14") (pin "2") (pinfunction "2_2") (pintype "passive"))
      (node (ref "C15") (pin "2") (pinfunction "2_2") (pintype "passive"))
      (node (ref "C16") (pin "2") (pinfunction "2_2") (pintype "passive"))
      (node (ref "C17") (pin "1") (pinfunction "1_1") (pintype "passive"))
      (node (ref "C18") (pin "1") (pinfunction "1_1") (pintype "passive"))
      (node (ref "C19") (pin "2") (pinfunction "2_2") (pintype "passive"))
      (node (ref "C2") (pin "2") (pinfunction "2_2") (pintype "passive"))
      (node (ref "C20") (pin "2") (pinfunction "2_2") (pintype "passive"))
      (node (ref "C22") (pin "2") (pinfunction "2_2") (pintype "passive"))
      (node (ref "C23") (pin "1") (pinfunction "1_1") (pintype "passive"))
      (node (ref "C24") (pin "1") (pinfunction "1_1") (pintype "passive"))
      (node (ref "C25") (pin "2") (pinfunction "2_2") (pintype "passive"))
      (node (ref "C27") (pin "1") (pinfunction "1_1") (pintype "passive"))
      (node (ref "C29") (pin "1") (pinfunction "1_1") (pintype "passive"))
      (node (ref "C3") (pin "2") (pinfunction "2_2") (pintype "passive"))
      (node (ref "C30") (pin "1") (pinfunction "1_1") (pintype "passive"))
      (node (ref "C31") (pin "1") (pinfunction "1_1") (pintype "passive"))
      (node (ref "C32") (pin "1") (pinfunction "1_1") (pintype "passive"))
      (node (ref "C33") (pin "2") (pinfunction "2_2") (pintype "passive"))
      (node (ref "C34") (pin "1") (pinfunction "1_1") (pintype "passive"))
      (node (ref "C37") (pin "2") (pinfunction "2_2") (pintype "passive"))
      (node (ref "C38") (pin "2") (pinfunction "2_2") (pintype "passive"))
      (node (ref "C39") (pin "2") (pinfunction "2_2") (pintype "passive"))
      (node (ref "C4") (pin "2") (pinfunction "2_2") (pintype "passive"))
      (node (ref "C42") (pin "2") (pinfunction "2_2") (pintype "passive"))
      (node (ref "C43") (pin "2") (pinfunction "2_2") (pintype "passive"))
      (node (ref "C5") (pin "2") (pinfunction "2_2") (pintype "passive"))
      (node (ref "C6") (pin "2") (pinfunction "2_2") (pintype "passive"))
      (node (ref "C8") (pin "2") (pinfunction "2_2") (pintype "passive"))
      (node (ref "C9") (pin "2") (pinfunction "2_2") (pintype "passive"))
      (node (ref "D3") (pin "2") (pinfunction "GND_2") (pintype "bidirectional"))
      (node (ref "D4") (pin "1") (pinfunction "K_1") (pintype "bidirectional"))
      (node (ref "EPD_C1") (pin "1") (pinfunction "1_1") (pintype "passive"))
      (node (ref "EPD_C10") (pin "1") (pinfunction "1_1") (pintype "passive"))
      (node (ref "EPD_C11") (pin "1") (pinfunction "1_1") (pintype "passive"))
      (node (ref "EPD_C12") (pin "1") (pinfunction "1_1") (pintype "passive"))
      (node (ref "EPD_C2") (pin "1") (pinfunction "1_1") (pintype "passive"))
      (node (ref "EPD_C5") (pin "1") (pinfunction "1_1") (pintype "passive"))
      (node (ref "EPD_C6") (pin "1") (pinfunction "1_1") (pintype "passive"))
      (node (ref "EPD_C7") (pin "1") (pinfunction "1_1") (pintype "passive"))
      (node (ref "EPD_C8") (pin "1") (pinfunction "1_1") (pintype "passive"))
      (node (ref "EPD_C9") (pin "1") (pinfunction "1_1") (pintype "passive"))
      (node (ref "IC1") (pin "D2") (pinfunction "GND_D2") (pintype "bidirectional"))
      (node (ref "IC2") (pin "B1") (pinfunction "IN/TRIG_B1") (pintype "bidirectional"))
      (node (ref "IC2") (pin "B3") (pinfunction "GND_B3") (pintype "bidirectional"))
      (node (ref "IC3") (pin "8") (pinfunction "GNDIO_8") (pintype "bidirectional"))
      (node (ref "IC3") (pin "9") (pinfunction "GND_9") (pintype "bidirectional"))
      (node (ref "IC9") (pin "B1") (pinfunction "VSEL_B1") (pintype "bidirectional"))
      (node (ref "IC9") (pin "C1") (pinfunction "AGND_C1") (pintype "bidirectional"))
      (node (ref "IC9") (pin "C2") (pinfunction "PGND_1_C2") (pintype "bidirectional"))
      (node (ref "IC9") (pin "C3") (pinfunction "PGND_2_C3") (pintype "bidirectional"))
      (node (ref "J1") (pin "17") (pinfunction "17_17") (pintype "bidirectional"))
      (node (ref "J1") (pin "8") (pinfunction "8_8") (pintype "bidirectional"))
      (node (ref "J1") (pin "MP1") (pinfunction "MP1_MP1") (pintype "bidirectional"))
      (node (ref "J1") (pin "MP2") (pinfunction "MP2_MP2") (pintype "bidirectional"))
      (node (ref "J2") (pin "3") (pinfunction "3_3") (pintype "bidirectional"))
      (node (ref "J2") (pin "5") (pinfunction "5_5") (pintype "bidirectional"))
      (node (ref "J4") (pin "A12_B1") (pinfunction "GND_A12_B1") (pintype "power_in"))
      (node (ref "J4") (pin "A1_B12") (pinfunction "GND_A1_B12") (pintype "power_in"))
      (node (ref "J4") (pin "SH1") (pinfunction "SHIELD_SH1") (pintype "passive"))
      (node (ref "J4") (pin "SH2") (pinfunction "SHIELD_SH2") (pintype "passive"))
      (node (ref "J4") (pin "SH3") (pinfunction "SHIELD_SH3") (pintype "passive"))
      (node (ref "J4") (pin "SH4") (pinfunction "SHIELD_SH4") (pintype "passive"))
      (node (ref "R1") (pin "1") (pinfunction "1_1") (pintype "bidirectional"))
      (node (ref "R1_USB") (pin "1") (pinfunction "1_1") (pintype "bidirectional"))
      (node (ref "R2-EP-DR") (pin "1") (pinfunction "1_1") (pintype "bidirectional"))
      (node (ref "R2_USB") (pin "2") (pinfunction "2_2") (pintype "bidirectional"))
      (node (ref "R9") (pin "1") (pinfunction "1_1") (pintype "bidirectional"))
      (node (ref "R_TYPE_SEL") (pin "1") (pinfunction "1_1") (pintype "bidirectional"))
      (node (ref "SJ1") (pin "1") (pinfunction "1_1") (pintype "passive"))
      (node (ref "SW_DN") (pin "1") (pinfunction "1_1") (pintype "passive"))
      (node (ref "SW_ENT") (pin "1") (pinfunction "1_1") (pintype "passive"))
      (node (ref "SW_UP") (pin "1") (pinfunction "1_1") (pintype "passive"))
      (node (ref "TP_BAT_GND") (pin "TP") (pinfunction "TP_TP") (pintype "input"))
      (node (ref "TP_GND") (pin "TP") (pinfunction "TP_TP") (pintype "input"))
      (node (ref "U$1") (pin "2") (pinfunction "2_2") (pintype "passive"))
      (node (ref "U$19") (pin "2") (pinfunction "2_2") (pintype "passive"))
      (node (ref "U1") (pin "P$74") (pinfunction "VSS_PAD_P$74") (pintype "bidirectional"))
      (node (ref "U1") (pin "P$75") (pinfunction "VSS_PAD_P$75") (pintype "bidirectional"))
      (node (ref "U1") (pin "P$76") (pinfunction "VSS_PAD_P$76") (pintype "bidirectional"))
      (node (ref "U1") (pin "P$77") (pinfunction "VSS_PAD_P$77") (pintype "bidirectional"))
      (node (ref "U1") (pin "P$78") (pinfunction "VSS_PAD_P$78") (pintype "bidirectional"))
      (node (ref "U1") (pin "P$79") (pinfunction "VSS_PAD_P$79") (pintype "bidirectional"))
      (node (ref "U1") (pin "P$80") (pinfunction "VSS_PAD_P$80") (pintype "bidirectional"))
      (node (ref "U1") (pin "P$81") (pinfunction "VSS_PAD_P$81") (pintype "bidirectional"))
      (node (ref "U1") (pin "P$82") (pinfunction "VSS_PAD_P$82") (pintype "bidirectional"))
      (node (ref "U1") (pin "P$83") (pinfunction "VSS_PAD_P$83") (pintype "bidirectional"))
      (node (ref "U1") (pin "P$84") (pinfunction "VSS_PAD_P$84") (pintype "bidirectional"))
      (node (ref "U1") (pin "P$85") (pinfunction "VSS_PAD_P$85") (pintype "bidirectional"))
      (node (ref "U1") (pin "P$86") (pinfunction "VSS_PAD_P$86") (pintype "bidirectional"))
      (node (ref "U1") (pin "P$87") (pinfunction "VSS_PAD_P$87") (pintype "bidirectional"))
      (node (ref "U1") (pin "P$88") (pinfunction "VSS_PAD_P$88") (pintype "bidirectional"))
      (node (ref "U1") (pin "P$89") (pinfunction "VSS_PAD_P$89") (pintype "bidirectional"))
      (node (ref "U1") (pin "P$90") (pinfunction "VSS_PAD_P$90") (pintype "bidirectional"))
      (node (ref "U1") (pin "P$B7") (pinfunction "VSS_P$B7") (pintype "power_in"))
      (node (ref "U1") (pin "P$F23") (pinfunction "VSS_PA_P$F23") (pintype "bidirectional"))
      (node (ref "U3") (pin "1") (pinfunction "CTG_1") (pintype "power_in"))
      (node (ref "U3") (pin "4") (pinfunction "GND_4") (pintype "power_in"))
      (node (ref "U3") (pin "6") (pinfunction "QSTRT_6") (pintype "input"))
      (node (ref "U3") (pin "9") (pinfunction "EP_9") (pintype "power_in"))
      (node (ref "X1") (pin "2") (pinfunction "2_2") (pintype "passive"))
      (node (ref "X1") (pin "4") (pinfunction "4_4") (pintype "passive"))
    )
    (net (code "18") (name "HAPTIC_EN") (class "Default")
      (node (ref "IC2") (pin "A1") (pinfunction "EN_A1") (pintype "bidirectional"))
      (node (ref "U1") (pin "P$U1") (pinfunction "P0.12_P$U1") (pintype "bidirectional"))
    )
    (net (code "19") (name "IMU_INT1") (class "Default")
      (node (ref "IC3") (pin "5") (pinfunction "INT1_5") (pintype "bidirectional"))
      (node (ref "U1") (pin "P$N1") (pinfunction "P0.08_P$N1") (pintype "bidirectional"))
    )
    (net (code "20") (name "IMU_INT2") (class "Default")
      (node (ref "IC3") (pin "6") (pinfunction "INT2_6") (pintype "bidirectional"))
      (node (ref "U1") (pin "P$P2") (pinfunction "P1.08_P$P2") (pintype "bidirectional"))
    )
    (net (code "21") (name "LX1") (class "Default")
      (node (ref "IC9") (pin "B2") (pinfunction "SW1_1_B2") (pintype "bidirectional"))
      (node (ref "IC9") (pin "B3") (pinfunction "SW1_2_B3") (pintype "bidirectional"))
      (node (ref "L7") (pin "1") (pinfunction "1_1") (pintype "bidirectional"))
    )
    (net (code "22") (name "LX2") (class "Default")
      (node (ref "IC9") (pin "D2") (pinfunction "SW2_1_D2") (pintype "bidirectional"))
      (node (ref "IC9") (pin "D3") (pinfunction "SW2_2_D3") (pintype "bidirectional"))
      (node (ref "L7") (pin "2") (pinfunction "2_2") (pintype "bidirectional"))
    )
    (net (code "23") (name "MOSI") (class "Default")
      (node (ref "J1") (pin "14") (pinfunction "14_14") (pintype "bidirectional"))
      (node (ref "U1") (pin "P$B13") (pinfunction "P0.03/AIN1_P$B13") (pintype "bidirectional"))
    )
    (net (code "24") (name "Net-(D2-K)") (class "Default")
      (node (ref "C2-EP-DR") (pin "1") (pinfunction "1_1") (pintype "passive"))
      (node (ref "D2") (pin "1") (pinfunction "K_1") (pintype "bidirectional"))
      (node (ref "D4") (pin "2") (pinfunction "A_2") (pintype "bidirectional"))
    )
    (net (code "25") (name "Net-(D5-A)") (class "Default")
      (node (ref "C2-EP-DR") (pin "2") (pinfunction "2_2") (pintype "passive"))
      (node (ref "D5") (pin "2") (pinfunction "A_2") (pintype "bidirectional"))
      (node (ref "L4") (pin "2") (pinfunction "2_2") (pintype "bidirectional"))
      (node (ref "Q3") (pin "3") (pinfunction "D_3") (pintype "bidirectional"))
    )
    (net (code "26") (name "Net-(EPD_C1-Pad2)") (class "Default")
      (node (ref "EPD_C1") (pin "2") (pinfunction "2_2") (pintype "passive"))
      (node (ref "J1") (pin "5") (pinfunction "5_5") (pintype "bidirectional"))
    )
    (net (code "27") (name "Net-(EPD_C2-Pad2)") (class "Default")
      (node (ref "EPD_C2") (pin "2") (pinfunction "2_2") (pintype "passive"))
      (node (ref "J1") (pin "4") (pinfunction "4_4") (pintype "bidirectional"))
    )
    (net (code "28") (name "Net-(EPD_C6-Pad2)") (class "Default")
      (node (ref "EPD_C6") (pin "2") (pinfunction "2_2") (pintype "passive"))
      (node (ref "J1") (pin "18") (pinfunction "18_18") (pintype "bidirectional"))
    )
    (net (code "29") (name "Net-(EPD_C7-Pad2)") (class "Default")
      (node (ref "EPD_C7") (pin "2") (pinfunction "2_2") (pintype "passive"))
      (node (ref "J1") (pin "19") (pinfunction "19_19") (pintype "bidirectional"))
    )
    (net (code "30") (name "Net-(EPD_C8-Pad2)") (class "Default")
      (node (ref "EPD_C8") (pin "2") (pinfunction "2_2") (pintype "passive"))
      (node (ref "J1") (pin "20") (pinfunction "20_20") (pintype "bidirectional"))
    )
    (net (code "31") (name "Net-(EPD_C10-Pad2)") (class "Default")
      (node (ref "EPD_C10") (pin "2") (pinfunction "2_2") (pintype "passive"))
      (node (ref "J1") (pin "22") (pinfunction "22_22") (pintype "bidirectional"))
    )
    (net (code "32") (name "Net-(EPD_C12-Pad2)") (class "Default")
      (node (ref "EPD_C12") (pin "2") (pinfunction "2_2") (pintype "passive"))
      (node (ref "J1") (pin "24") (pinfunction "24_24") (pintype "bidirectional"))
    )
    (net (code "33") (name "Net-(IC1-TS{slash}MR)") (class "Default")
      (node (ref "IC1") (pin "D1") (pinfunction "TS/MR_D1") (pintype "bidirectional"))
      (node (ref "R9") (pin "2") (pinfunction "2_2") (pintype "bidirectional"))
    )
    (net (code "34") (name "Net-(IC2-REG)") (class "Default")
      (node (ref "C32") (pin "2") (pinfunction "2_2") (pintype "passive"))
      (node (ref "IC2") (pin "A2") (pinfunction "REG_A2") (pintype "bidirectional"))
    )
    (net (code "35") (name "Net-(IC3-SDO)") (class "Default")
      (node (ref "IC3") (pin "1") (pinfunction "SDO_1") (pintype "bidirectional"))
      (node (ref "R1") (pin "2") (pinfunction "2_2") (pintype "bidirectional"))
    )
    (net (code "36") (name "Net-(IC9-SCL)") (class "Default")
      (node (ref "IC9") (pin "D1") (pinfunction "SCL_D1") (pintype "bidirectional"))
      (node (ref "R4") (pin "2") (pinfunction "2_2") (pintype "bidirectional"))
    )
    (net (code "37") (name "Net-(IC9-SDA)") (class "Default")
      (node (ref "IC9") (pin "E1") (pinfunction "SDA_E1") (pintype "bidirectional"))
      (node (ref "R2") (pin "2") (pinfunction "2_2") (pintype "bidirectional"))
    )
    (net (code "38") (name "Net-(J4-CC1)") (class "Default")
      (node (ref "J4") (pin "A5") (pinfunction "CC1_A5") (pintype "bidirectional"))
      (node (ref "R1_USB") (pin "2") (pinfunction "2_2") (pintype "bidirectional"))
    )
    (net (code "39") (name "Net-(J4-CC2)") (class "Default")
      (node (ref "J4") (pin "B5") (pinfunction "CC2_B5") (pintype "bidirectional"))
      (node (ref "R2_USB") (pin "1") (pinfunction "1_1") (pintype "bidirectional"))
    )
    (net (code "40") (name "Net-(L2-Pad2)") (class "Default")
      (node (ref "L2") (pin "2") (pinfunction "2_2") (pintype "bidirectional"))
      (node (ref "L3") (pin "1") (pinfunction "1_1") (pintype "bidirectional"))
    )
    (net (code "41") (name "Net-(R1-EP-DR-Pad1)") (class "Default")
      (node (ref "R1-EP-DR") (pin "1") (pinfunction "1_1") (pintype "bidirectional"))
      (node (ref "R_TYPE_SEL") (pin "2") (pinfunction "2_2") (pintype "bidirectional"))
      (node (ref "SJ1") (pin "2") (pinfunction "2_2") (pintype "passive"))
    )
    (net (code "42") (name "Net-(U1-ANT)") (class "Default")
      (node (ref "C3") (pin "1") (pinfunction "1_1") (pintype "passive"))
      (node (ref "L1") (pin "1") (pinfunction "1_1") (pintype "bidirectional"))
      (node (ref "U1") (pin "P$H23") (pinfunction "ANT_P$H23") (pintype "bidirectional"))
    )
    (net (code "43") (name "Net-(U1-DCC)") (class "Default")
      (node (ref "L2") (pin "1") (pinfunction "1_1") (pintype "bidirectional"))
      (node (ref "U1") (pin "P$B3") (pinfunction "DCC_P$B3") (pintype "output"))
    )
    (net (code "44") (name "Net-(U1-DEC2)") (class "Default")
      (node (ref "C13") (pin "1") (pinfunction "1_1") (pintype "passive"))
      (node (ref "U1") (pin "P$A18") (pinfunction "DEC2_P$A18") (pintype "bidirectional"))
    )
    (net (code "45") (name "Net-(U1-DEC3V3)") (class "Default")
      (node (ref "C20") (pin "1") (pinfunction "1_1") (pintype "passive"))
      (node (ref "U1") (pin "P$AC5") (pinfunction "DEC3V3_P$AC5") (pintype "bidirectional"))
    )
    (net (code "46") (name "Net-(U1-DEC5)") (class "Default")
      (node (ref "C9") (pin "1") (pinfunction "1_1") (pintype "passive"))
      (node (ref "U1") (pin "P$N24") (pinfunction "DEC5_P$N24") (pintype "bidirectional"))
    )
    (net (code "47") (name "Net-(U1-P0.00{slash}XL1)") (class "Default")
      (node (ref "C18") (pin "2") (pinfunction "2_2") (pintype "passive"))
      (node (ref "U1") (pin "P$D2") (pinfunction "P0.00/XL1_P$D2") (pintype "bidirectional"))
      (node (ref "X2") (pin "2") (pinfunction "2_2") (pintype "passive"))
    )
    (net (code "48") (name "Net-(U1-P0.01{slash}XL2)") (class "Default")
      (node (ref "C17") (pin "2") (pinfunction "2_2") (pintype "passive"))
      (node (ref "U1") (pin "P$F2") (pinfunction "P0.01/XL2_P$F2") (pintype "bidirectional"))
      (node (ref "X2") (pin "1") (pinfunction "1_1") (pintype "passive"))
    )
    (net (code "49") (name "Net-(U1-XC1)") (class "Default")
      (node (ref "C1") (pin "1") (pinfunction "1_1") (pintype "passive"))
      (node (ref "U1") (pin "P$B24") (pinfunction "XC1_P$B24") (pintype "input"))
      (node (ref "X1") (pin "1") (pinfunction "1_1") (pintype "passive"))
    )
    (net (code "50") (name "Net-(U1-XC2)") (class "Default")
      (node (ref "C2") (pin "1") (pinfunction "1_1") (pintype "passive"))
      (node (ref "U1") (pin "P$A23") (pinfunction "XC2_P$A23") (pintype "output"))
      (node (ref "X1") (pin "3") (pinfunction "3_3") (pintype "passive"))
    )
    (net (code "51") (name "OUT+") (class "Default")
      (node (ref "IC2") (pin "A3") (pinfunction "OUT+_A3") (pintype "bidirectional"))
      (node (ref "TP1") (pin "TP") (pinfunction "TP_TP") (pintype "input"))
    )
    (net (code "52") (name "OUT-") (class "Default")
      (node (ref "IC2") (pin "C3") (pinfunction "OUT-_C3") (pintype "bidirectional"))
      (node (ref "TP2") (pin "TP") (pinfunction "TP_TP") (pintype "input"))
    )
    (net (code "53") (name "P0.04") (class "Default")
      (node (ref "U1") (pin "P$J1") (pinfunction "P0.04/AIN2_P$J1") (pintype "bidirectional"))
    )
    (net (code "54") (name "P0.09") (class "Default")
      (node (ref "U1") (pin "P$L24") (pinfunction "P0.09/NFC1_P$L24") (pintype "bidirectional"))
    )
    (net (code "55") (name "P0.13") (class "Default")
      (node (ref "C30") (pin "2") (pinfunction "2_2") (pintype "passive"))
      (node (ref "R5") (pin "1") (pinfunction "1_1") (pintype "bidirectional"))
      (node (ref "SW_UP") (pin "2") (pinfunction "2_2") (pintype "passive"))
      (node (ref "U1") (pin "P$AD8") (pinfunction "P0.13_P$AD8") (pintype "bidirectional"))
    )
    (net (code "56") (name "P0.14") (class "Default")
      (node (ref "C31") (pin "2") (pinfunction "2_2") (pintype "passive"))
      (node (ref "R8") (pin "1") (pinfunction "1_1") (pintype "bidirectional"))
      (node (ref "SW_ENT") (pin "2") (pinfunction "2_2") (pintype "passive"))
      (node (ref "U1") (pin "P$AC9") (pinfunction "P0.14_P$AC9") (pintype "bidirectional"))
    )
    (net (code "57") (name "P0.19") (class "Default")
      (node (ref "U1") (pin "P$AC15") (pinfunction "P0.19_P$AC15") (pintype "bidirectional"))
    )
    (net (code "58") (name "P0.20") (class "Default")
      (node (ref "U1") (pin "P$AD16") (pinfunction "P0.20_P$AD16") (pintype "bidirectional"))
    )
    (net (code "59") (name "P0.21") (class "Default")
      (node (ref "U1") (pin "P$AC17") (pinfunction "P0.21_P$AC17") (pintype "bidirectional"))
    )
    (net (code "60") (name "P0.22") (class "Default")
      (node (ref "U1") (pin "P$AD18") (pinfunction "P0.22_P$AD18") (pintype "bidirectional"))
    )
    (net (code "61") (name "P0.23") (class "Default")
      (node (ref "U1") (pin "P$AC19") (pinfunction "P0.23_P$AC19") (pintype "bidirectional"))
    )
    (net (code "62") (name "P0.24") (class "Default")
      (node (ref "U1") (pin "P$AD20") (pinfunction "P0.24_P$AD20") (pintype "bidirectional"))
    )
    (net (code "63") (name "P0.25") (class "Default")
      (node (ref "U1") (pin "P$AC21") (pinfunction "P0.25_P$AC21") (pintype "bidirectional"))
    )
    (net (code "64") (name "P0.26") (class "Default")
      (node (ref "U1") (pin "P$G1") (pinfunction "P0.26_P$G1") (pintype "bidirectional"))
    )
    (net (code "65") (name "P0.27") (class "Default")
      (node (ref "U1") (pin "P$H2") (pinfunction "P0.27_P$H2") (pintype "bidirectional"))
    )
    (net (code "66") (name "P0.28") (class "Default")
      (node (ref "U1") (pin "P$B11") (pinfunction "P0.28/AIN4_P$B11") (pintype "bidirectional"))
    )
    (net (code "67") (name "P0.29") (class "Default")
      (node (ref "U1") (pin "P$A10") (pinfunction "P0.29/AIN5_P$A10") (pintype "bidirectional"))
    )
    (net (code "68") (name "P0.30") (class "Default")
      (node (ref "U1") (pin "P$B9") (pinfunction "P0.30/AIN6_P$B9") (pintype "bidirectional"))
    )
    (net (code "69") (name "P0.31") (class "Default")
      (node (ref "U1") (pin "P$A8") (pinfunction "P0.31/AIN7_P$A8") (pintype "bidirectional"))
    )
    (net (code "70") (name "P1.01") (class "Default")
      (node (ref "Q1") (pin "1") (pinfunction "G_1") (pintype "bidirectional"))
      (node (ref "R_PWR_EPD") (pin "1") (pinfunction "1_1") (pintype "bidirectional"))
      (node (ref "U1") (pin "P$Y23") (pinfunction "P1.01_P$Y23") (pintype "bidirectional"))
    )
    (net (code "71") (name "P1.02") (class "Default")
      (node (ref "C29") (pin "2") (pinfunction "2_2") (pintype "passive"))
      (node (ref "R7") (pin "1") (pinfunction "1_1") (pintype "bidirectional"))
      (node (ref "SW_DN") (pin "2") (pinfunction "2_2") (pintype "passive"))
      (node (ref "U1") (pin "P$W24") (pinfunction "P1.02_P$W24") (pintype "bidirectional"))
    )
    (net (code "72") (name "P1.03") (class "Default")
      (node (ref "U1") (pin "P$V23") (pinfunction "P1.03_P$V23") (pintype "bidirectional"))
    )
    (net (code "73") (name "P1.04") (class "Default")
      (node (ref "U1") (pin "P$U24") (pinfunction "P1.04_P$U24") (pintype "bidirectional"))
    )
    (net (code "74") (name "P1.05") (class "Default")
      (node (ref "U1") (pin "P$T23") (pinfunction "P1.05_P$T23") (pintype "bidirectional"))
    )
    (net (code "75") (name "P1.06") (class "Default")
      (node (ref "U1") (pin "P$R24") (pinfunction "P1.06_P$R24") (pintype "bidirectional"))
    )
    (net (code "76") (name "P1.07") (class "Default")
      (node (ref "U1") (pin "P$P23") (pinfunction "P1.07_P$P23") (pintype "bidirectional"))
    )
    (net (code "77") (name "P1.09") (class "Default")
      (node (ref "U1") (pin "P$R1") (pinfunction "P1.09_P$R1") (pintype "bidirectional"))
    )
    (net (code "78") (name "P1.10") (class "Default")
      (node (ref "U1") (pin "P$A20") (pinfunction "P1.10_P$A20") (pintype "bidirectional"))
    )
    (net (code "79") (name "P1.11") (class "Default")
      (node (ref "U1") (pin "P$B19") (pinfunction "P1.11_P$B19") (pintype "bidirectional"))
    )
    (net (code "80") (name "P1.12") (class "Default")
      (node (ref "U1") (pin "P$B17") (pinfunction "P1.12_P$B17") (pintype "bidirectional"))
    )
    (net (code "81") (name "P1.13") (class "Default")
      (node (ref "U1") (pin "P$A16") (pinfunction "P1.13_P$A16") (pintype "bidirectional"))
    )
    (net (code "82") (name "P1.14") (class "Default")
      (node (ref "U1") (pin "P$B15") (pinfunction "P1.14_P$B15") (pintype "bidirectional"))
    )
    (net (code "83") (name "P1.15") (class "Default")
      (node (ref "U1") (pin "P$A14") (pinfunction "P1.15_P$A14") (pintype "bidirectional"))
    )
    (net (code "84") (name "PMIC_INT") (class "Default")
      (node (ref "IC1") (pin "A1") (pinfunction "~{INT}_A1") (pintype "bidirectional"))
      (node (ref "U1") (pin "P$T2") (pinfunction "P0.11_P$T2") (pintype "bidirectional"))
    )
    (net (code "85") (name "PREVGH") (class "Default")
      (node (ref "D5") (pin "1") (pinfunction "K_1") (pintype "bidirectional"))
      (node (ref "EPD_C9") (pin "2") (pinfunction "2_2") (pintype "passive"))
      (node (ref "J1") (pin "21") (pinfunction "21_21") (pintype "bidirectional"))
    )
    (net (code "86") (name "PREVGL") (class "Default")
      (node (ref "D2") (pin "2") (pinfunction "A_2") (pintype "bidirectional"))
      (node (ref "EPD_C11") (pin "2") (pinfunction "2_2") (pintype "passive"))
      (node (ref "J1") (pin "23") (pinfunction "23_23") (pintype "bidirectional"))
    )
    (net (code "87") (name "RESE") (class "Default")
      (node (ref "J1") (pin "3") (pinfunction "3_3") (pintype "bidirectional"))
      (node (ref "Q3") (pin "2") (pinfunction "S_2") (pintype "bidirectional"))
      (node (ref "R1-EP-DR") (pin "2") (pinfunction "2_2") (pintype "bidirectional"))
    )
    (net (code "88") (name "RESET") (class "Default")
      (node (ref "J2") (pin "6") (pinfunction "6_6") (pintype "bidirectional"))
      (node (ref "TP_RESET") (pin "TP") (pinfunction "TP_TP") (pintype "input"))
      (node (ref "U1") (pin "P$AC13") (pinfunction "P0.18/RESET_P$AC13") (pintype "bidirectional"))
    )
    (net (code "89") (name "RF") (class "Default")
      (node (ref "ANT1") (pin "1") (pinfunction "FEED_1") (pintype "input"))
      (node (ref "C22") (pin "1") (pinfunction "1_1") (pintype "passive"))
      (node (ref "C4") (pin "1") (pinfunction "1_1") (pintype "passive"))
      (node (ref "L1") (pin "2") (pinfunction "2_2") (pintype "bidirectional"))
    )
    (net (code "90") (name "SCK") (class "Default")
      (node (ref "J1") (pin "13") (pinfunction "13_13") (pintype "bidirectional"))
      (node (ref "U1") (pin "P$A12") (pinfunction "P0.02/AIN0_P$A12") (pintype "bidirectional"))
    )
    (net (code "91") (name "SCL") (class "Default")
      (node (ref "IC1") (pin "B1") (pinfunction "SCL_B1") (pintype "bidirectional"))
      (node (ref "IC2") (pin "C1") (pinfunction "SCL_C1") (pintype "bidirectional"))
      (node (ref "IC3") (pin "12") (pinfunction "SCX_12") (pintype "bidirectional"))
      (node (ref "R17") (pin "2") (pinfunction "2_2") (pintype "bidirectional"))
      (node (ref "R4") (pin "1") (pinfunction "1_1") (pintype "bidirectional"))
      (node (ref "TP_SCL") (pin "TP") (pinfunction "TP_TP") (pintype "input"))
      (node (ref "U1") (pin "P$M2") (pinfunction "P0.07_P$M2") (pintype "bidirectional"))
      (node (ref "U3") (pin "7") (pinfunction "SCL_7") (pintype "input"))
    )
    (net (code "92") (name "SDA") (class "Default")
      (node (ref "IC1") (pin "C1") (pinfunction "SDA_C1") (pintype "bidirectional"))
      (node (ref "IC2") (pin "B2") (pinfunction "SDA_B2") (pintype "bidirectional"))
      (node (ref "IC3") (pin "2") (pinfunction "SDX_2") (pintype "bidirectional"))
      (node (ref "R18") (pin "2") (pinfunction "2_2") (pintype "bidirectional"))
      (node (ref "R2") (pin "1") (pinfunction "1_1") (pintype "bidirectional"))
      (node (ref "TP_SDA") (pin "TP") (pinfunction "TP_TP") (pintype "input"))
      (node (ref "U1") (pin "P$L1") (pinfunction "P0.06_P$L1") (pintype "bidirectional"))
      (node (ref "U3") (pin "8") (pinfunction "SDA_8") (pintype "bidirectional"))
    )
    (net (code "93") (name "SWDCLK") (class "Default")
      (node (ref "J2") (pin "4") (pinfunction "4_4") (pintype "bidirectional"))
      (node (ref "TP_SWDCLK") (pin "TP") (pinfunction "TP_TP") (pintype "input"))
      (node (ref "U1") (pin "P$AA24") (pinfunction "SWDCLK_P$AA24") (pintype "input"))
    )
    (net (code "94") (name "SWDIO") (class "Default")
      (node (ref "J2") (pin "2") (pinfunction "2_2") (pintype "bidirectional"))
      (node (ref "TP_SWDIO") (pin "TP") (pinfunction "TP_TP") (pintype "input"))
      (node (ref "U1") (pin "P$AC24") (pinfunction "SWDIO_P$AC24") (pintype "bidirectional"))
    )
    (net (code "95") (name "SWO") (class "Default")
      (node (ref "TP_SWO") (pin "TP") (pinfunction "TP_TP") (pintype "input"))
      (node (ref "U1") (pin "P$AD22") (pinfunction "P1.00_P$AD22") (pintype "bidirectional"))
    )
    (net (code "96") (name "VBAT") (class "Default")
      (node (ref "C27") (pin "2") (pinfunction "2_2") (pintype "passive"))
      (node (ref "C37") (pin "1") (pinfunction "1_1") (pintype "passive"))
      (node (ref "IC1") (pin "C2") (pinfunction "BAT_C2") (pintype "bidirectional"))
      (node (ref "TP_VBAT") (pin "TP") (pinfunction "TP_TP") (pintype "input"))
      (node (ref "U3") (pin "2") (pinfunction "CELL_2") (pintype "power_in"))
      (node (ref "U3") (pin "3") (pinfunction "VDD_3") (pintype "power_in"))
    )
    (net (code "97") (name "VBUS") (class "Default")
      (node (ref "C38") (pin "1") (pinfunction "1_1") (pintype "passive"))
      (node (ref "C42") (pin "1") (pinfunction "1_1") (pintype "passive"))
      (node (ref "C43") (pin "1") (pinfunction "1_1") (pintype "passive"))
      (node (ref "D3") (pin "5") (pinfunction "VBUS_5") (pintype "bidirectional"))
      (node (ref "IC1") (pin "A2") (pinfunction "IN_A2") (pintype "bidirectional"))
      (node (ref "J4") (pin "A4_B9") (pinfunction "VBUS_A4_B9") (pintype "power_in"))
      (node (ref "J4") (pin "A9_B4") (pinfunction "VBUS_A9_B4") (pintype "power_in"))
      (node (ref "U$1") (pin "1") (pinfunction "1_1") (pintype "passive"))
      (node (ref "U1") (pin "P$AD2") (pinfunction "VBUS_P$AD2") (pintype "power_in"))
    )
    (net (code "98") (name "VREG") (class "Default")
      (node (ref "C23") (pin "2") (pinfunction "2_2") (pintype "passive"))
      (node (ref "C24") (pin "2") (pinfunction "2_2") (pintype "passive"))
      (node (ref "C39") (pin "1") (pinfunction "1_1") (pintype "passive"))
      (node (ref "IC1") (pin "B2") (pinfunction "SYS_B2") (pintype "bidirectional"))
      (node (ref "IC9") (pin "A1") (pinfunction "EN_A1") (pintype "bidirectional"))
      (node (ref "IC9") (pin "A2") (pinfunction "VIN_1_A2") (pintype "bidirectional"))
      (node (ref "IC9") (pin "A3") (pinfunction "VIN_2_A3") (pintype "bidirectional"))
      (node (ref "TP_VREG") (pin "TP") (pinfunction "TP_TP") (pintype "input"))
    )
    (net (code "99") (name "unconnected-(ANT1-NC-Pad2)") (class "Default")
      (node (ref "ANT1") (pin "2") (pinfunction "NC_2") (pintype "no_connect"))
    )
    (net (code "100") (name "unconnected-(IC3-ASCL-Pad11)") (class "Default")
      (node (ref "IC3") (pin "11") (pinfunction "ASCL_11") (pintype "bidirectional"))
    )
    (net (code "101") (name "unconnected-(IC3-ASDA-Pad4)") (class "Default")
      (node (ref "IC3") (pin "4") (pinfunction "ASDA_4") (pintype "bidirectional"))
    )
    (net (code "102") (name "unconnected-(J1-Pad1)") (class "Default")
      (node (ref "J1") (pin "1") (pinfunction "1_1") (pintype "bidirectional"))
    )
    (net (code "103") (name "unconnected-(J1-Pad6)") (class "Default")
      (node (ref "J1") (pin "6") (pinfunction "6_6") (pintype "bidirectional"))
    )
    (net (code "104") (name "unconnected-(J1-Pad7)") (class "Default")
      (node (ref "J1") (pin "7") (pinfunction "7_7") (pintype "bidirectional"))
    )
    (net (code "105") (name "unconnected-(J4-SBU1-PadA8)") (class "Default")
      (node (ref "J4") (pin "A8") (pinfunction "SBU1_A8") (pintype "bidirectional"))
    )
    (net (code "106") (name "unconnected-(J4-SBU2-PadB8)") (class "Default")
      (node (ref "J4") (pin "B8") (pinfunction "SBU2_B8") (pintype "bidirectional"))
    )
    (net (code "107") (name "unconnected-(U1-DCCH-PadP$AB2)") (class "Default")
      (node (ref "U1") (pin "P$AB2") (pinfunction "DCCH_P$AB2") (pintype "bidirectional"))
    )
  )
)
